# SCH_Boom-Crane-Body_2025-03-01.net
KiCad netlist of a schematic drawn in EasyEDA
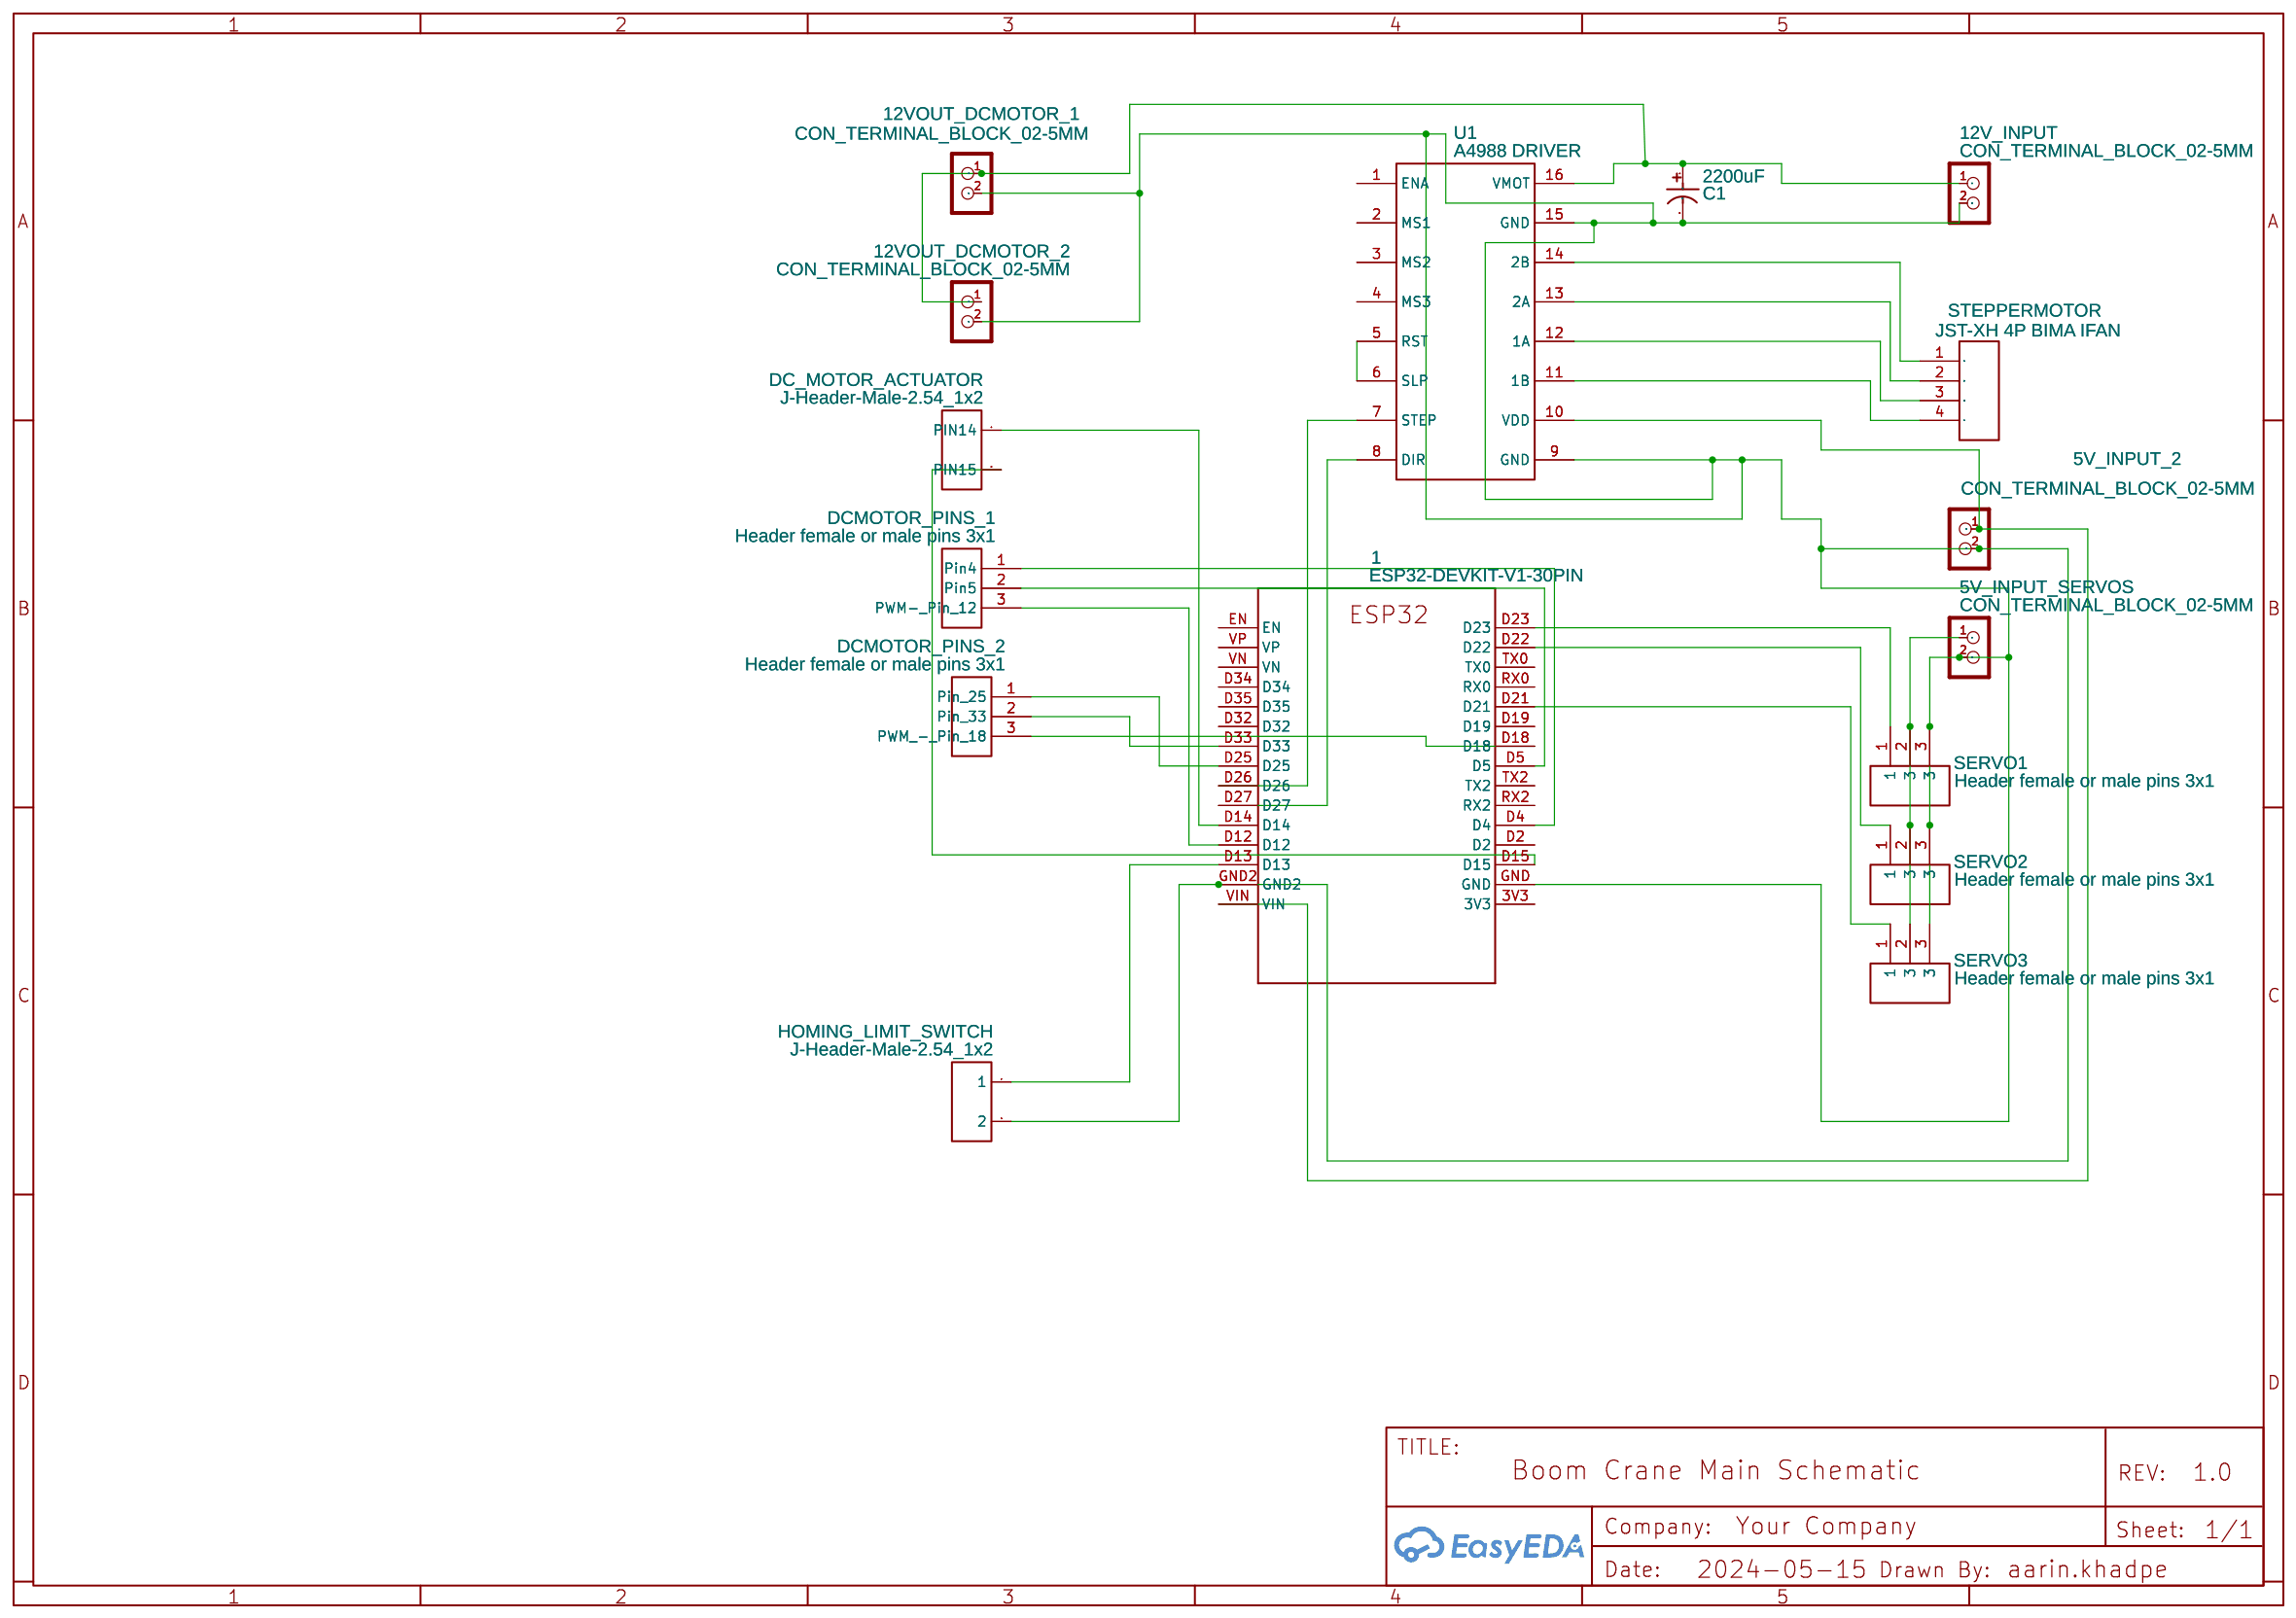
[diagram p0: schematic sheet]

(export (version "E")
  (design (tool "Eeschema 10.0.6"))
  (components
    (comp (ref "1") (value "ESP32-DEVKIT-V1-30PIN") (libsource (lib "") (part "ESP32-DEVKIT-V1-30PIN")))
    (comp (ref "5V_INPUT_2")
      (value "CON_TERMINAL_BLOCK_02-5MM")
      (libsource (lib "") (part "CON_TERMINAL_BLOCK_02-5MM_3"))
    )
    (comp (ref "5V_INPUT_SERVOS")
      (value "CON_TERMINAL_BLOCK_02-5MM")
      (libsource (lib "") (part "CON_TERMINAL_BLOCK_02-5MM"))
    )
    (comp (ref "12VOUT_DCMOTOR_1")
      (value "CON_TERMINAL_BLOCK_02-5MM")
      (libsource (lib "") (part "CON_TERMINAL_BLOCK_02-5MM_1"))
    )
    (comp (ref "12VOUT_DCMOTOR_2")
      (value "CON_TERMINAL_BLOCK_02-5MM")
      (libsource (lib "") (part "CON_TERMINAL_BLOCK_02-5MM_1"))
    )
    (comp (ref "12V_INPUT")
      (value "CON_TERMINAL_BLOCK_02-5MM")
      (libsource (lib "") (part "CON_TERMINAL_BLOCK_02-5MM_2"))
    )
    (comp (ref "C1")
      (value "2200uF")
      (fields (field (name "Manufacturer Part") "16ZLH680MEFC8X16") (field (name "Manufacturer") "Rubycon"))
      (libsource (lib "") (part "2200uF"))
    )
    (comp (ref "DCMOTOR_PINS_1")
      (value "Header female or male pins 3x1")
      (libsource (lib "") (part "Header female or male pins 3x1"))
    )
    (comp (ref "DCMOTOR_PINS_2")
      (value "Header female or male pins 3x1")
      (libsource (lib "") (part "Header female or male pins 3x1_2"))
    )
    (comp (ref "DC_MOTOR_ACTUATOR")
      (value "J-Header-Male-2.54_1x2")
      (fields (field (name "Manufacturer Part") "826629-2") (field (name "Manufacturer") "TE Connectivity"))
      (libsource (lib "") (part "J-Header-Male-2.54_1x2"))
    )
    (comp (ref "HOMING_LIMIT_SWITCH")
      (value "J-Header-Male-2.54_1x2")
      (fields (field (name "Manufacturer Part") "826629-2") (field (name "Manufacturer") "TE Connectivity"))
      (libsource (lib "") (part "J-Header-Male-2.54_1x2_1"))
    )
    (comp (ref "SERVO1")
      (value "Header female or male pins 3x1")
      (libsource (lib "") (part "Header female or male pins 3x1_1"))
    )
    (comp (ref "SERVO2")
      (value "Header female or male pins 3x1")
      (libsource (lib "") (part "Header female or male pins 3x1_1"))
    )
    (comp (ref "SERVO3")
      (value "Header female or male pins 3x1")
      (libsource (lib "") (part "Header female or male pins 3x1_1"))
    )
    (comp (ref "STEPPERMOTOR")
      (value "JST-XH 4P BIMA IFAN")
      (libsource (lib "") (part "JST-XH 4P BIMA IFAN"))
    )
    (comp (ref "U1") (value "A4988 DRIVER") (libsource (lib "") (part "A4988 DRIVER")))
  )
  (nets
    (net (code "1") (name "Net-(1-PadD13)") (class "Default")
      (node (ref "1") (pin "D13") (pinfunction "D13_D13") (pintype "unspecified"))
      (node (ref "HOMING_LIMIT_SWITCH") (pin "1") (pinfunction "1_1") (pintype "unspecified"))
    )
    (net (code "2") (name "Net-(1-PadD21)") (class "Default")
      (node (ref "1") (pin "D21") (pinfunction "D21_D21") (pintype "unspecified"))
      (node (ref "SERVO3") (pin "1") (pinfunction "1_1") (pintype "unspecified"))
    )
    (net (code "3") (name "Net-(1-PadD22)") (class "Default")
      (node (ref "1") (pin "D22") (pinfunction "D22_D22") (pintype "unspecified"))
      (node (ref "SERVO2") (pin "1") (pinfunction "1_1") (pintype "unspecified"))
    )
    (net (code "4") (name "Net-(1-PadD23)") (class "Default")
      (node (ref "1") (pin "D23") (pinfunction "D23_D23") (pintype "unspecified"))
      (node (ref "SERVO1") (pin "1") (pinfunction "1_1") (pintype "unspecified"))
    )
    (net (code "5") (name "Net-(1-PadGND)") (class "Default")
      (node (ref "1") (pin "GND") (pinfunction "GND_GND") (pintype "unspecified"))
      (node (ref "1") (pin "GND2") (pinfunction "GND2_GND2") (pintype "unspecified"))
      (node (ref "12VOUT_DCMOTOR_1") (pin "2") (pinfunction "2_2") (pintype "unspecified"))
      (node (ref "12VOUT_DCMOTOR_2") (pin "2") (pinfunction "2_2") (pintype "unspecified"))
      (node (ref "12V_INPUT") (pin "2") (pinfunction "2_2") (pintype "unspecified"))
      (node (ref "5V_INPUT_2") (pin "2") (pinfunction "2_2") (pintype "unspecified"))
      (node (ref "5V_INPUT_SERVOS") (pin "2") (pinfunction "2_2") (pintype "unspecified"))
      (node (ref "C1") (pin "2") (pinfunction "2_2") (pintype "input"))
      (node (ref "HOMING_LIMIT_SWITCH") (pin "2") (pinfunction "2_2") (pintype "unspecified"))
      (node (ref "SERVO1") (pin "3") (pinfunction "3_3") (pintype "unspecified"))
      (node (ref "SERVO2") (pin "3") (pinfunction "3_3") (pintype "unspecified"))
      (node (ref "SERVO3") (pin "3") (pinfunction "3_3") (pintype "unspecified"))
      (node (ref "U1") (pin "15") (pinfunction "GND_15") (pintype "unspecified"))
      (node (ref "U1") (pin "9") (pinfunction "GND_9") (pintype "unspecified"))
    )
    (net (code "6") (name "Net-(5V_INPUT_SERVOS-Pad1)") (class "Default")
      (node (ref "5V_INPUT_SERVOS") (pin "1") (pinfunction "1_1") (pintype "unspecified"))
      (node (ref "SERVO1") (pin "2") (pinfunction "3_2") (pintype "unspecified"))
      (node (ref "SERVO2") (pin "2") (pinfunction "3_2") (pintype "unspecified"))
      (node (ref "SERVO3") (pin "2") (pinfunction "3_2") (pintype "unspecified"))
    )
    (net (code "7") (name "Net-(DCMOTOR_PINS_1-PWM-_Pin_12)") (class "Default")
      (node (ref "1") (pin "D12") (pinfunction "D12_D12") (pintype "unspecified"))
      (node (ref "DCMOTOR_PINS_1") (pin "3") (pinfunction "PWM-_Pin_12_3") (pintype "unspecified"))
    )
    (net (code "8") (name "Net-(DCMOTOR_PINS_1-Pin4)") (class "Default")
      (node (ref "1") (pin "D4") (pinfunction "D4_D4") (pintype "unspecified"))
      (node (ref "DCMOTOR_PINS_1") (pin "1") (pinfunction "Pin4_1") (pintype "unspecified"))
    )
    (net (code "9") (name "Net-(DCMOTOR_PINS_1-Pin5)") (class "Default")
      (node (ref "1") (pin "D5") (pinfunction "D5_D5") (pintype "unspecified"))
      (node (ref "DCMOTOR_PINS_1") (pin "2") (pinfunction "Pin5_2") (pintype "unspecified"))
    )
    (net (code "10") (name "Net-(DCMOTOR_PINS_2-PWM_-_Pin_18)") (class "Default")
      (node (ref "1") (pin "D18") (pinfunction "D18_D18") (pintype "unspecified"))
      (node (ref "DCMOTOR_PINS_2") (pin "3") (pinfunction "PWM_-_Pin_18_3") (pintype "unspecified"))
    )
    (net (code "11") (name "Net-(DCMOTOR_PINS_2-Pin_25)") (class "Default")
      (node (ref "1") (pin "D25") (pinfunction "D25_D25") (pintype "unspecified"))
      (node (ref "DCMOTOR_PINS_2") (pin "1") (pinfunction "Pin_25_1") (pintype "unspecified"))
    )
    (net (code "12") (name "Net-(DCMOTOR_PINS_2-Pin_33)") (class "Default")
      (node (ref "1") (pin "D33") (pinfunction "D33_D33") (pintype "unspecified"))
      (node (ref "DCMOTOR_PINS_2") (pin "2") (pinfunction "Pin_33_2") (pintype "unspecified"))
    )
    (net (code "13") (name "Net-(DC_MOTOR_ACTUATOR-PIN14)") (class "Default")
      (node (ref "1") (pin "D14") (pinfunction "D14_D14") (pintype "unspecified"))
      (node (ref "DC_MOTOR_ACTUATOR") (pin "1") (pinfunction "PIN14_1") (pintype "unspecified"))
    )
    (net (code "14") (name "Net-(DC_MOTOR_ACTUATOR-PIN15)") (class "Default")
      (node (ref "1") (pin "D15") (pinfunction "D15_D15") (pintype "unspecified"))
      (node (ref "DC_MOTOR_ACTUATOR") (pin "2") (pinfunction "PIN15_2") (pintype "unspecified"))
    )
    (net (code "15") (name "Net-(U1-1A)") (class "Default")
      (node (ref "STEPPERMOTOR") (pin "3") (pinfunction "3_3") (pintype "unspecified"))
      (node (ref "U1") (pin "12") (pinfunction "1A_12") (pintype "unspecified"))
    )
    (net (code "16") (name "Net-(U1-1B)") (class "Default")
      (node (ref "STEPPERMOTOR") (pin "4") (pinfunction "4_4") (pintype "unspecified"))
      (node (ref "U1") (pin "11") (pinfunction "1B_11") (pintype "unspecified"))
    )
    (net (code "17") (name "Net-(U1-2A)") (class "Default")
      (node (ref "STEPPERMOTOR") (pin "2") (pinfunction "2_2") (pintype "unspecified"))
      (node (ref "U1") (pin "13") (pinfunction "2A_13") (pintype "unspecified"))
    )
    (net (code "18") (name "Net-(U1-2B)") (class "Default")
      (node (ref "STEPPERMOTOR") (pin "1") (pinfunction "1_1") (pintype "unspecified"))
      (node (ref "U1") (pin "14") (pinfunction "2B_14") (pintype "unspecified"))
    )
    (net (code "19") (name "Net-(U1-DIR)") (class "Default")
      (node (ref "1") (pin "D27") (pinfunction "D27_D27") (pintype "unspecified"))
      (node (ref "U1") (pin "8") (pinfunction "DIR_8") (pintype "unspecified"))
    )
    (net (code "20") (name "Net-(U1-RST)") (class "Default")
      (node (ref "U1") (pin "5") (pinfunction "RST_5") (pintype "unspecified"))
      (node (ref "U1") (pin "6") (pinfunction "SLP_6") (pintype "unspecified"))
    )
    (net (code "21") (name "Net-(U1-STEP)") (class "Default")
      (node (ref "1") (pin "D26") (pinfunction "D26_D26") (pintype "unspecified"))
      (node (ref "U1") (pin "7") (pinfunction "STEP_7") (pintype "unspecified"))
    )
    (net (code "22") (name "Net-(U1-VDD)") (class "Default")
      (node (ref "1") (pin "VIN") (pinfunction "VIN_VIN") (pintype "unspecified"))
      (node (ref "5V_INPUT_2") (pin "1") (pinfunction "1_1") (pintype "unspecified"))
      (node (ref "U1") (pin "10") (pinfunction "VDD_10") (pintype "unspecified"))
    )
    (net (code "23") (name "Net-(U1-VMOT)") (class "Default")
      (node (ref "12VOUT_DCMOTOR_1") (pin "1") (pinfunction "1_1") (pintype "unspecified"))
      (node (ref "12VOUT_DCMOTOR_2") (pin "1") (pinfunction "1_1") (pintype "unspecified"))
      (node (ref "12V_INPUT") (pin "1") (pinfunction "1_1") (pintype "unspecified"))
      (node (ref "C1") (pin "1") (pinfunction "1_1") (pintype "input"))
      (node (ref "U1") (pin "16") (pinfunction "VMOT_16") (pintype "unspecified"))
    )
    (net (code "24") (name "unconnected-(1-Pad3V3)") (class "Default")
      (node (ref "1") (pin "3V3") (pinfunction "3V3_3V3") (pintype "unspecified"))
    )
    (net (code "25") (name "unconnected-(1-PadD2)") (class "Default")
      (node (ref "1") (pin "D2") (pinfunction "D2_D2") (pintype "unspecified"))
    )
    (net (code "26") (name "unconnected-(1-PadD19)") (class "Default")
      (node (ref "1") (pin "D19") (pinfunction "D19_D19") (pintype "unspecified"))
    )
    (net (code "27") (name "unconnected-(1-PadD32)") (class "Default")
      (node (ref "1") (pin "D32") (pinfunction "D32_D32") (pintype "unspecified"))
    )
    (net (code "28") (name "unconnected-(1-PadD34)") (class "Default")
      (node (ref "1") (pin "D34") (pinfunction "D34_D34") (pintype "unspecified"))
    )
    (net (code "29") (name "unconnected-(1-PadD35)") (class "Default")
      (node (ref "1") (pin "D35") (pinfunction "D35_D35") (pintype "unspecified"))
    )
    (net (code "30") (name "unconnected-(1-PadEN)") (class "Default")
      (node (ref "1") (pin "EN") (pinfunction "EN_EN") (pintype "unspecified"))
    )
    (net (code "31") (name "unconnected-(1-PadRX0)") (class "Default")
      (node (ref "1") (pin "RX0") (pinfunction "RX0_RX0") (pintype "unspecified"))
    )
    (net (code "32") (name "unconnected-(1-PadRX2)") (class "Default")
      (node (ref "1") (pin "RX2") (pinfunction "RX2_RX2") (pintype "unspecified"))
    )
    (net (code "33") (name "unconnected-(1-PadTX0)") (class "Default")
      (node (ref "1") (pin "TX0") (pinfunction "TX0_TX0") (pintype "unspecified"))
    )
    (net (code "34") (name "unconnected-(1-PadTX2)") (class "Default")
      (node (ref "1") (pin "TX2") (pinfunction "TX2_TX2") (pintype "unspecified"))
    )
    (net (code "35") (name "unconnected-(1-PadVN)") (class "Default")
      (node (ref "1") (pin "VN") (pinfunction "VN_VN") (pintype "unspecified"))
    )
    (net (code "36") (name "unconnected-(1-PadVP)") (class "Default")
      (node (ref "1") (pin "VP") (pinfunction "VP_VP") (pintype "unspecified"))
    )
    (net (code "37") (name "unconnected-(U1-ENA-Pad1)") (class "Default")
      (node (ref "U1") (pin "1") (pinfunction "ENA_1") (pintype "unspecified"))
    )
    (net (code "38") (name "unconnected-(U1-MS1-Pad2)") (class "Default")
      (node (ref "U1") (pin "2") (pinfunction "MS1_2") (pintype "unspecified"))
    )
    (net (code "39") (name "unconnected-(U1-MS2-Pad3)") (class "Default")
      (node (ref "U1") (pin "3") (pinfunction "MS2_3") (pintype "unspecified"))
    )
    (net (code "40") (name "unconnected-(U1-MS3-Pad4)") (class "Default")
      (node (ref "U1") (pin "4") (pinfunction "MS3_4") (pintype "unspecified"))
    )
  )
)
